# WiFiLed.net
KiCad netlist of a schematic drawn in EAGLE
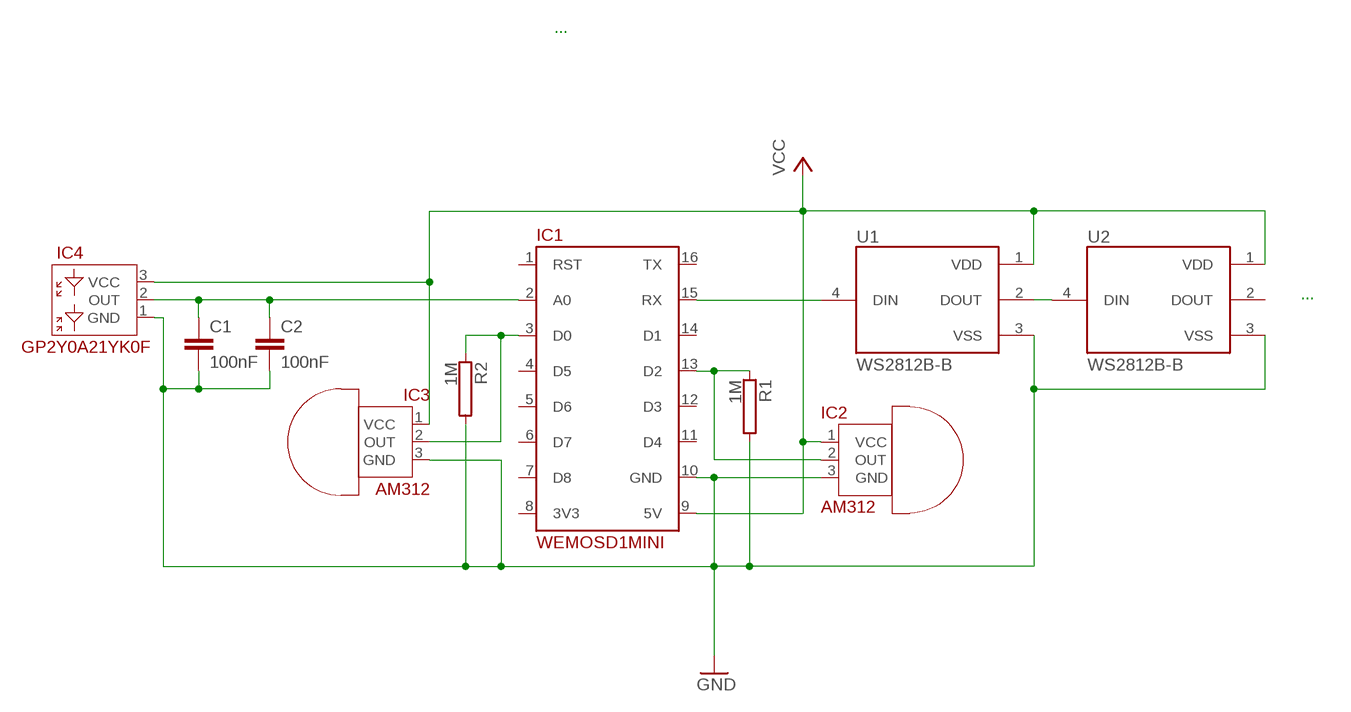
[diagram p0: schematic, sheet 1]

(export (version "E")
  (design (tool "Eeschema 10.0.6"))
  (components
    (comp (ref "C1")
      (value "100nF")
      (footprint "eagle-import:C2.5-3")
      (libsource (lib "eagle-import") (part "C2,5-3"))
    )
    (comp (ref "C2")
      (value "100nF")
      (footprint "eagle-import:C2.5-3")
      (libsource (lib "eagle-import") (part "C2,5-3"))
    )
    (comp (ref "IC1")
      (value "WEMOSD1MINI")
      (footprint "eagle-import:ESP32_DIL16")
      (libsource (lib "eagle-import") (part "WEMOSD1MINI"))
    )
    (comp (ref "IC2")
      (value "AM312")
      (footprint "eagle-import:AM312")
      (libsource (lib "eagle-import") (part "AM312"))
    )
    (comp (ref "IC3")
      (value "AM312")
      (footprint "eagle-import:AM312")
      (libsource (lib "eagle-import") (part "AM312"))
    )
    (comp (ref "IC4")
      (value "GP2Y0A21YK0F")
      (footprint "eagle-import:GP2Y0A21YK0F")
      (libsource (lib "eagle-import") (part "GP2Y0A21YK0F"))
    )
    (comp (ref "R1")
      (value "1M")
      (footprint "eagle-import:AC01")
      (libsource (lib "eagle-import") (part "RAC01"))
    )
    (comp (ref "R2")
      (value "1M")
      (footprint "eagle-import:AC01")
      (libsource (lib "eagle-import") (part "RAC01"))
    )
    (comp (ref "U1")
      (value "WS2812B-B")
      (footprint "eagle-import:LED_WS2812B-B")
      (fields (field (name "MF") "Worldsemi"))
      (libsource (lib "eagle-import") (part "WS2812B-B"))
    )
    (comp (ref "U2")
      (value "WS2812B-B")
      (footprint "eagle-import:LED_WS2812B-B")
      (fields (field (name "MF") "Worldsemi"))
      (libsource (lib "eagle-import") (part "WS2812B-B"))
    )
  )
  (nets
    (net (code "1") (name "GND") (class "Default")
      (node (ref "C1") (pin "2") (pinfunction "2_2") (pintype "passive"))
      (node (ref "C2") (pin "2") (pinfunction "2_2") (pintype "passive"))
      (node (ref "IC1") (pin "10") (pinfunction "GND_10") (pintype "bidirectional"))
      (node (ref "IC2") (pin "3") (pinfunction "GND_3") (pintype "bidirectional"))
      (node (ref "IC3") (pin "3") (pinfunction "GND_3") (pintype "bidirectional"))
      (node (ref "IC4") (pin "1") (pinfunction "GND_1") (pintype "bidirectional"))
      (node (ref "R1") (pin "2") (pinfunction "2_2") (pintype "passive"))
      (node (ref "R2") (pin "2") (pinfunction "2_2") (pintype "passive"))
      (node (ref "U1") (pin "3") (pinfunction "VSS_3") (pintype "power_in"))
      (node (ref "U2") (pin "3") (pinfunction "VSS_3") (pintype "power_in"))
    )
    (net (code "2") (name "Net-(IC1-A0)") (class "Default")
      (node (ref "C1") (pin "1") (pinfunction "1_1") (pintype "passive"))
      (node (ref "C2") (pin "1") (pinfunction "1_1") (pintype "passive"))
      (node (ref "IC1") (pin "2") (pinfunction "A0_2") (pintype "bidirectional"))
      (node (ref "IC4") (pin "2") (pinfunction "OUT_2") (pintype "bidirectional"))
    )
    (net (code "3") (name "Net-(IC1-D0)") (class "Default")
      (node (ref "IC1") (pin "3") (pinfunction "D0_3") (pintype "bidirectional"))
      (node (ref "IC3") (pin "2") (pinfunction "OUT_2") (pintype "output"))
      (node (ref "R2") (pin "1") (pinfunction "1_1") (pintype "passive"))
    )
    (net (code "4") (name "Net-(IC1-D2)") (class "Default")
      (node (ref "IC1") (pin "13") (pinfunction "D2_13") (pintype "bidirectional"))
      (node (ref "IC2") (pin "2") (pinfunction "OUT_2") (pintype "output"))
      (node (ref "R1") (pin "1") (pinfunction "1_1") (pintype "passive"))
    )
    (net (code "5") (name "Net-(IC1-RX)") (class "Default")
      (node (ref "IC1") (pin "15") (pinfunction "RX_15") (pintype "bidirectional"))
      (node (ref "U1") (pin "4") (pinfunction "DIN_4") (pintype "input"))
    )
    (net (code "6") (name "Net-(U1-DOUT)") (class "Default")
      (node (ref "U1") (pin "2") (pinfunction "DOUT_2") (pintype "output"))
      (node (ref "U2") (pin "4") (pinfunction "DIN_4") (pintype "input"))
    )
    (net (code "7") (name "VCC") (class "Default")
      (node (ref "IC1") (pin "9") (pinfunction "5V_9") (pintype "power_in"))
      (node (ref "IC2") (pin "1") (pinfunction "VCC_1") (pintype "bidirectional"))
      (node (ref "IC3") (pin "1") (pinfunction "VCC_1") (pintype "bidirectional"))
      (node (ref "IC4") (pin "3") (pinfunction "VCC_3") (pintype "bidirectional"))
      (node (ref "U1") (pin "1") (pinfunction "VDD_1") (pintype "power_in"))
      (node (ref "U2") (pin "1") (pinfunction "VDD_1") (pintype "power_in"))
    )
    (net (code "8") (name "unconnected-(IC1-3V3-Pad8)") (class "Default")
      (node (ref "IC1") (pin "8") (pinfunction "3V3_8") (pintype "bidirectional"))
    )
    (net (code "9") (name "unconnected-(IC1-D1-Pad14)") (class "Default")
      (node (ref "IC1") (pin "14") (pinfunction "D1_14") (pintype "bidirectional"))
    )
    (net (code "10") (name "unconnected-(IC1-D3-Pad12)") (class "Default")
      (node (ref "IC1") (pin "12") (pinfunction "D3_12") (pintype "bidirectional"))
    )
    (net (code "11") (name "unconnected-(IC1-D4-Pad11)") (class "Default")
      (node (ref "IC1") (pin "11") (pinfunction "D4_11") (pintype "bidirectional"))
    )
    (net (code "12") (name "unconnected-(IC1-D5-Pad4)") (class "Default")
      (node (ref "IC1") (pin "4") (pinfunction "D5_4") (pintype "bidirectional"))
    )
    (net (code "13") (name "unconnected-(IC1-D6-Pad5)") (class "Default")
      (node (ref "IC1") (pin "5") (pinfunction "D6_5") (pintype "bidirectional"))
    )
    (net (code "14") (name "unconnected-(IC1-D7-Pad6)") (class "Default")
      (node (ref "IC1") (pin "6") (pinfunction "D7_6") (pintype "bidirectional"))
    )
    (net (code "15") (name "unconnected-(IC1-D8-Pad7)") (class "Default")
      (node (ref "IC1") (pin "7") (pinfunction "D8_7") (pintype "bidirectional"))
    )
    (net (code "16") (name "unconnected-(IC1-RST-Pad1)") (class "Default")
      (node (ref "IC1") (pin "1") (pinfunction "RST_1") (pintype "input"))
    )
    (net (code "17") (name "unconnected-(IC1-TX-Pad16)") (class "Default")
      (node (ref "IC1") (pin "16") (pinfunction "TX_16") (pintype "bidirectional"))
    )
    (net (code "18") (name "unconnected-(U2-DOUT-Pad2)") (class "Default")
      (node (ref "U2") (pin "2") (pinfunction "DOUT_2") (pintype "output"))
    )
  )
)
